# HF0R0.net
KiCad netlist of a schematic drawn in EAGLE
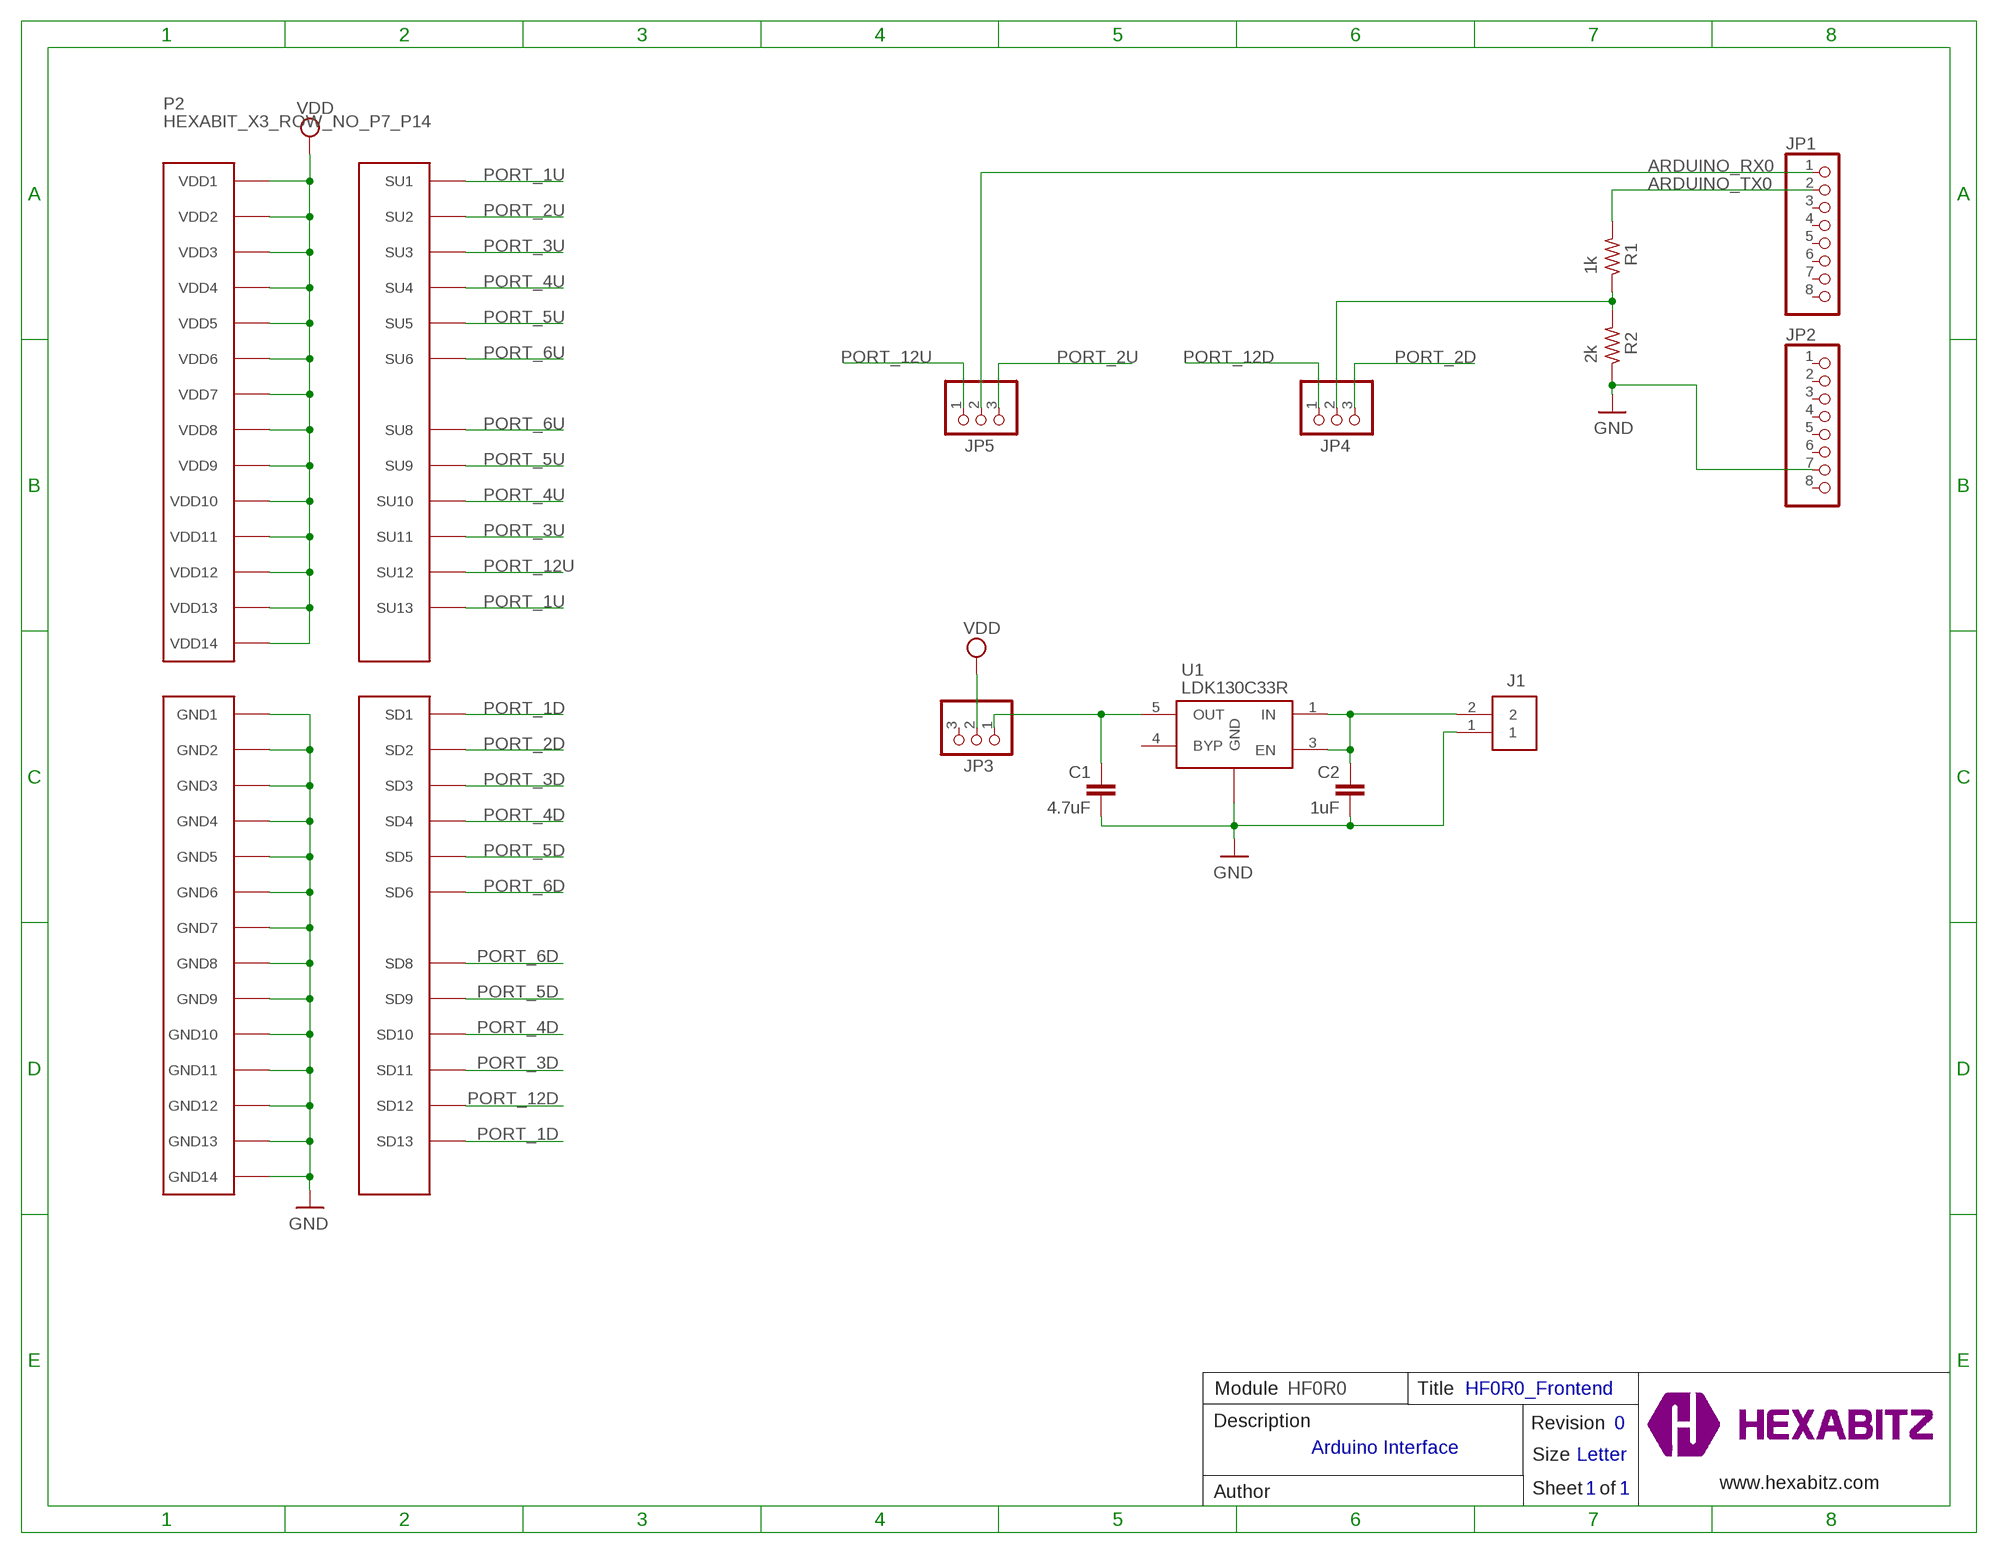
[diagram p0: schematic, sheet 1]

(export (version "E")
  (design (tool "Eeschema 10.0.6"))
  (components
    (comp (ref "C1")
      (value "4.7uF")
      (footprint "eagle-import:C-0805")
      (libsource (lib "eagle-import") (part "C-0805"))
    )
    (comp (ref "C2")
      (value "1uF")
      (footprint "eagle-import:C-0805")
      (libsource (lib "eagle-import") (part "C-0805"))
    )
    (comp (ref "J1")
      (value "3-644456-2")
      (footprint "eagle-import:TE_3-644456-2")
      (fields (field (name "MF") "TE Connectivity") (field (name "MPN") "87224-1"))
      (libsource (lib "eagle-import") (part "3-644456-2"))
    )
    (comp (ref "JP1")
      (value "PINHD-1X8")
      (footprint "eagle-import:1X08")
      (libsource (lib "eagle-import") (part "PINHD-1X8"))
    )
    (comp (ref "JP2")
      (value "PINHD-1X8")
      (footprint "eagle-import:1X08")
      (libsource (lib "eagle-import") (part "PINHD-1X8"))
    )
    (comp (ref "JP3")
      (value "PINHD-1X3")
      (footprint "eagle-import:1X03")
      (libsource (lib "eagle-import") (part "PINHD-1X3"))
    )
    (comp (ref "JP4")
      (value "PINHD-1X3")
      (footprint "eagle-import:1X03")
      (libsource (lib "eagle-import") (part "PINHD-1X3"))
    )
    (comp (ref "JP5")
      (value "PINHD-1X3")
      (footprint "eagle-import:1X03")
      (libsource (lib "eagle-import") (part "PINHD-1X3"))
    )
    (comp (ref "P2")
      (value "HEXABIT_X3_ROW_NO_P7_P14")
      (footprint "eagle-import:HEXABIT_X3_ROW_NO_P7_P14")
      (libsource (lib "eagle-import") (part "HEXABIT_X3_ROW_NO_P7_P14"))
    )
    (comp (ref "R1")
      (value "1k")
      (footprint "eagle-import:R-0603")
      (libsource (lib "eagle-import") (part "R-0603"))
    )
    (comp (ref "R2")
      (value "2k")
      (footprint "eagle-import:R-0603")
      (libsource (lib "eagle-import") (part "R-0603"))
    )
    (comp (ref "U$1")
      (value "HEXABITZ-LOGO+SLOGAN")
      (footprint "eagle-import:HEXABITZ-LOGO+SLOGAN")
      (libsource (lib "eagle-import") (part "HEXABITZ-LOGO+SLOGAN"))
    )
    (comp (ref "U1")
      (value "LDK130C33R")
      (footprint "eagle-import:SOT65P210X110-5N")
      (fields (field (name "MOUSER_PART_NUMBER") "511-LDK130C33R"))
      (libsource (lib "eagle-import") (part "LDK130C33R"))
    )
  )
  (nets
    (net (code "1") (name "/ARDUINO_RX0") (class "Default")
      (node (ref "JP1") (pin "1") (pinfunction "1_1") (pintype "passive"))
      (node (ref "JP5") (pin "2") (pinfunction "2_2") (pintype "passive"))
    )
    (net (code "2") (name "/ARDUINO_TX0") (class "Default")
      (node (ref "JP1") (pin "2") (pinfunction "2_2") (pintype "passive"))
      (node (ref "R1") (pin "2") (pinfunction "2_2") (pintype "passive"))
    )
    (net (code "3") (name "/PORT_1D") (class "Default")
      (node (ref "P2") (pin "PAD_PD1") (pinfunction "SD1_PAD_PD1") (pintype "bidirectional"))
      (node (ref "P2") (pin "PAD_PD13") (pinfunction "SD13_PAD_PD13") (pintype "bidirectional"))
    )
    (net (code "4") (name "/PORT_1U") (class "Default")
      (node (ref "P2") (pin "PAD_PU1") (pinfunction "SU1_PAD_PU1") (pintype "bidirectional"))
      (node (ref "P2") (pin "PAD_PU13") (pinfunction "SU13_PAD_PU13") (pintype "bidirectional"))
    )
    (net (code "5") (name "/PORT_2D") (class "Default")
      (node (ref "JP4") (pin "3") (pinfunction "3_3") (pintype "passive"))
      (node (ref "P2") (pin "PAD_PD2") (pinfunction "SD2_PAD_PD2") (pintype "bidirectional"))
    )
    (net (code "6") (name "/PORT_2U") (class "Default")
      (node (ref "JP5") (pin "3") (pinfunction "3_3") (pintype "passive"))
      (node (ref "P2") (pin "PAD_PU2") (pinfunction "SU2_PAD_PU2") (pintype "bidirectional"))
    )
    (net (code "7") (name "/PORT_3D") (class "Default")
      (node (ref "P2") (pin "PAD_PD11") (pinfunction "SD11_PAD_PD11") (pintype "bidirectional"))
      (node (ref "P2") (pin "PAD_PD3") (pinfunction "SD3_PAD_PD3") (pintype "bidirectional"))
    )
    (net (code "8") (name "/PORT_3U") (class "Default")
      (node (ref "P2") (pin "PAD_PU11") (pinfunction "SU11_PAD_PU11") (pintype "bidirectional"))
      (node (ref "P2") (pin "PAD_PU3") (pinfunction "SU3_PAD_PU3") (pintype "bidirectional"))
    )
    (net (code "9") (name "/PORT_4D") (class "Default")
      (node (ref "P2") (pin "PAD_PD10") (pinfunction "SD10_PAD_PD10") (pintype "bidirectional"))
      (node (ref "P2") (pin "PAD_PD4") (pinfunction "SD4_PAD_PD4") (pintype "bidirectional"))
    )
    (net (code "10") (name "/PORT_4U") (class "Default")
      (node (ref "P2") (pin "PAD_PU10") (pinfunction "SU10_PAD_PU10") (pintype "bidirectional"))
      (node (ref "P2") (pin "PAD_PU4") (pinfunction "SU4_PAD_PU4") (pintype "bidirectional"))
    )
    (net (code "11") (name "/PORT_5D") (class "Default")
      (node (ref "P2") (pin "PAD_PD5") (pinfunction "SD5_PAD_PD5") (pintype "bidirectional"))
      (node (ref "P2") (pin "PAD_PD9") (pinfunction "SD9_PAD_PD9") (pintype "bidirectional"))
    )
    (net (code "12") (name "/PORT_5U") (class "Default")
      (node (ref "P2") (pin "PAD_PU5") (pinfunction "SU5_PAD_PU5") (pintype "bidirectional"))
      (node (ref "P2") (pin "PAD_PU9") (pinfunction "SU9_PAD_PU9") (pintype "bidirectional"))
    )
    (net (code "13") (name "/PORT_6D") (class "Default")
      (node (ref "P2") (pin "PAD_PD6") (pinfunction "SD6_PAD_PD6") (pintype "bidirectional"))
      (node (ref "P2") (pin "PAD_PD8") (pinfunction "SD8_PAD_PD8") (pintype "bidirectional"))
    )
    (net (code "14") (name "/PORT_6U") (class "Default")
      (node (ref "P2") (pin "PAD_PU6") (pinfunction "SU6_PAD_PU6") (pintype "bidirectional"))
      (node (ref "P2") (pin "PAD_PU8") (pinfunction "SU8_PAD_PU8") (pintype "bidirectional"))
    )
    (net (code "15") (name "/PORT_12D") (class "Default")
      (node (ref "JP4") (pin "1") (pinfunction "1_1") (pintype "passive"))
      (node (ref "P2") (pin "PAD_PD12") (pinfunction "SD12_PAD_PD12") (pintype "bidirectional"))
    )
    (net (code "16") (name "/PORT_12U") (class "Default")
      (node (ref "JP5") (pin "1") (pinfunction "1_1") (pintype "passive"))
      (node (ref "P2") (pin "PAD_PU12") (pinfunction "SU12_PAD_PU12") (pintype "bidirectional"))
    )
    (net (code "17") (name "GND") (class "Default")
      (node (ref "C1") (pin "2") (pinfunction "2_2") (pintype "passive"))
      (node (ref "C2") (pin "2") (pinfunction "2_2") (pintype "passive"))
      (node (ref "J1") (pin "1") (pinfunction "1_1") (pintype "passive"))
      (node (ref "JP2") (pin "7") (pinfunction "7_7") (pintype "passive"))
      (node (ref "P2") (pin "PAD_PD15") (pinfunction "GND1_PAD_PD15") (pintype "power_in"))
      (node (ref "P2") (pin "PAD_PD16") (pinfunction "GND2_PAD_PD16") (pintype "power_in"))
      (node (ref "P2") (pin "PAD_PD17") (pinfunction "GND3_PAD_PD17") (pintype "power_in"))
      (node (ref "P2") (pin "PAD_PD18") (pinfunction "GND4_PAD_PD18") (pintype "power_in"))
      (node (ref "P2") (pin "PAD_PD19") (pinfunction "GND5_PAD_PD19") (pintype "power_in"))
      (node (ref "P2") (pin "PAD_PD20") (pinfunction "GND6_PAD_PD20") (pintype "power_in"))
      (node (ref "P2") (pin "PAD_PD21") (pinfunction "GND7_PAD_PD21") (pintype "power_in"))
      (node (ref "P2") (pin "PAD_PD22") (pinfunction "GND8_PAD_PD22") (pintype "power_in"))
      (node (ref "P2") (pin "PAD_PD23") (pinfunction "GND9_PAD_PD23") (pintype "power_in"))
      (node (ref "P2") (pin "PAD_PD24") (pinfunction "GND10_PAD_PD24") (pintype "power_in"))
      (node (ref "P2") (pin "PAD_PD25") (pinfunction "GND11_PAD_PD25") (pintype "power_in"))
      (node (ref "P2") (pin "PAD_PD26") (pinfunction "GND12_PAD_PD26") (pintype "power_in"))
      (node (ref "P2") (pin "PAD_PD27") (pinfunction "GND13_PAD_PD27") (pintype "power_in"))
      (node (ref "P2") (pin "PAD_PD28") (pinfunction "GND14_PAD_PD28") (pintype "power_in"))
      (node (ref "R2") (pin "1") (pinfunction "1_1") (pintype "passive"))
      (node (ref "U1") (pin "2") (pinfunction "GND_2") (pintype "bidirectional"))
    )
    (net (code "18") (name "Net-(JP4-Pad2)") (class "Default")
      (node (ref "JP4") (pin "2") (pinfunction "2_2") (pintype "passive"))
      (node (ref "R1") (pin "1") (pinfunction "1_1") (pintype "passive"))
      (node (ref "R2") (pin "2") (pinfunction "2_2") (pintype "passive"))
    )
    (net (code "19") (name "Net-(U1-EN)") (class "Default")
      (node (ref "C2") (pin "1") (pinfunction "1_1") (pintype "passive"))
      (node (ref "J1") (pin "2") (pinfunction "2_2") (pintype "passive"))
      (node (ref "U1") (pin "1") (pinfunction "IN_1") (pintype "bidirectional"))
      (node (ref "U1") (pin "3") (pinfunction "EN_3") (pintype "bidirectional"))
    )
    (net (code "20") (name "Net-(U1-OUT)") (class "Default")
      (node (ref "C1") (pin "1") (pinfunction "1_1") (pintype "passive"))
      (node (ref "JP3") (pin "1") (pinfunction "1_1") (pintype "passive"))
      (node (ref "U1") (pin "5") (pinfunction "OUT_5") (pintype "bidirectional"))
    )
    (net (code "21") (name "VDD") (class "Default")
      (node (ref "JP3") (pin "2") (pinfunction "2_2") (pintype "passive"))
      (node (ref "P2") (pin "PAD_PU15") (pinfunction "VDD1_PAD_PU15") (pintype "power_in"))
      (node (ref "P2") (pin "PAD_PU16") (pinfunction "VDD2_PAD_PU16") (pintype "power_in"))
      (node (ref "P2") (pin "PAD_PU17") (pinfunction "VDD3_PAD_PU17") (pintype "power_in"))
      (node (ref "P2") (pin "PAD_PU18") (pinfunction "VDD4_PAD_PU18") (pintype "power_in"))
      (node (ref "P2") (pin "PAD_PU19") (pinfunction "VDD5_PAD_PU19") (pintype "power_in"))
      (node (ref "P2") (pin "PAD_PU20") (pinfunction "VDD6_PAD_PU20") (pintype "power_in"))
      (node (ref "P2") (pin "PAD_PU21") (pinfunction "VDD7_PAD_PU21") (pintype "power_in"))
      (node (ref "P2") (pin "PAD_PU22") (pinfunction "VDD8_PAD_PU22") (pintype "power_in"))
      (node (ref "P2") (pin "PAD_PU23") (pinfunction "VDD9_PAD_PU23") (pintype "power_in"))
      (node (ref "P2") (pin "PAD_PU24") (pinfunction "VDD10_PAD_PU24") (pintype "power_in"))
      (node (ref "P2") (pin "PAD_PU25") (pinfunction "VDD11_PAD_PU25") (pintype "power_in"))
      (node (ref "P2") (pin "PAD_PU26") (pinfunction "VDD12_PAD_PU26") (pintype "power_in"))
      (node (ref "P2") (pin "PAD_PU27") (pinfunction "VDD13_PAD_PU27") (pintype "power_in"))
      (node (ref "P2") (pin "PAD_PU28") (pinfunction "VDD14_PAD_PU28") (pintype "power_in"))
    )
    (net (code "22") (name "unconnected-(JP1-Pad3)") (class "Default")
      (node (ref "JP1") (pin "3") (pinfunction "3_3") (pintype "passive"))
    )
    (net (code "23") (name "unconnected-(JP1-Pad4)") (class "Default")
      (node (ref "JP1") (pin "4") (pinfunction "4_4") (pintype "passive"))
    )
    (net (code "24") (name "unconnected-(JP1-Pad5)") (class "Default")
      (node (ref "JP1") (pin "5") (pinfunction "5_5") (pintype "passive"))
    )
    (net (code "25") (name "unconnected-(JP1-Pad6)") (class "Default")
      (node (ref "JP1") (pin "6") (pinfunction "6_6") (pintype "passive"))
    )
    (net (code "26") (name "unconnected-(JP1-Pad7)") (class "Default")
      (node (ref "JP1") (pin "7") (pinfunction "7_7") (pintype "passive"))
    )
    (net (code "27") (name "unconnected-(JP1-Pad8)") (class "Default")
      (node (ref "JP1") (pin "8") (pinfunction "8_8") (pintype "passive"))
    )
    (net (code "28") (name "unconnected-(JP2-Pad1)") (class "Default")
      (node (ref "JP2") (pin "1") (pinfunction "1_1") (pintype "passive"))
    )
    (net (code "29") (name "unconnected-(JP2-Pad2)") (class "Default")
      (node (ref "JP2") (pin "2") (pinfunction "2_2") (pintype "passive"))
    )
    (net (code "30") (name "unconnected-(JP2-Pad3)") (class "Default")
      (node (ref "JP2") (pin "3") (pinfunction "3_3") (pintype "passive"))
    )
    (net (code "31") (name "unconnected-(JP2-Pad4)") (class "Default")
      (node (ref "JP2") (pin "4") (pinfunction "4_4") (pintype "passive"))
    )
    (net (code "32") (name "unconnected-(JP2-Pad5)") (class "Default")
      (node (ref "JP2") (pin "5") (pinfunction "5_5") (pintype "passive"))
    )
    (net (code "33") (name "unconnected-(JP2-Pad6)") (class "Default")
      (node (ref "JP2") (pin "6") (pinfunction "6_6") (pintype "passive"))
    )
    (net (code "34") (name "unconnected-(JP2-Pad8)") (class "Default")
      (node (ref "JP2") (pin "8") (pinfunction "8_8") (pintype "passive"))
    )
    (net (code "35") (name "unconnected-(JP3-Pad3)") (class "Default")
      (node (ref "JP3") (pin "3") (pinfunction "3_3") (pintype "passive"))
    )
    (net (code "36") (name "unconnected-(U1-BYP-Pad4)") (class "Default")
      (node (ref "U1") (pin "4") (pinfunction "BYP_4") (pintype "bidirectional"))
    )
  )
)
